# 5DPD8_v1_0_OS_Sheet2.net
KiCad netlist of a schematic drawn in Altium Designer
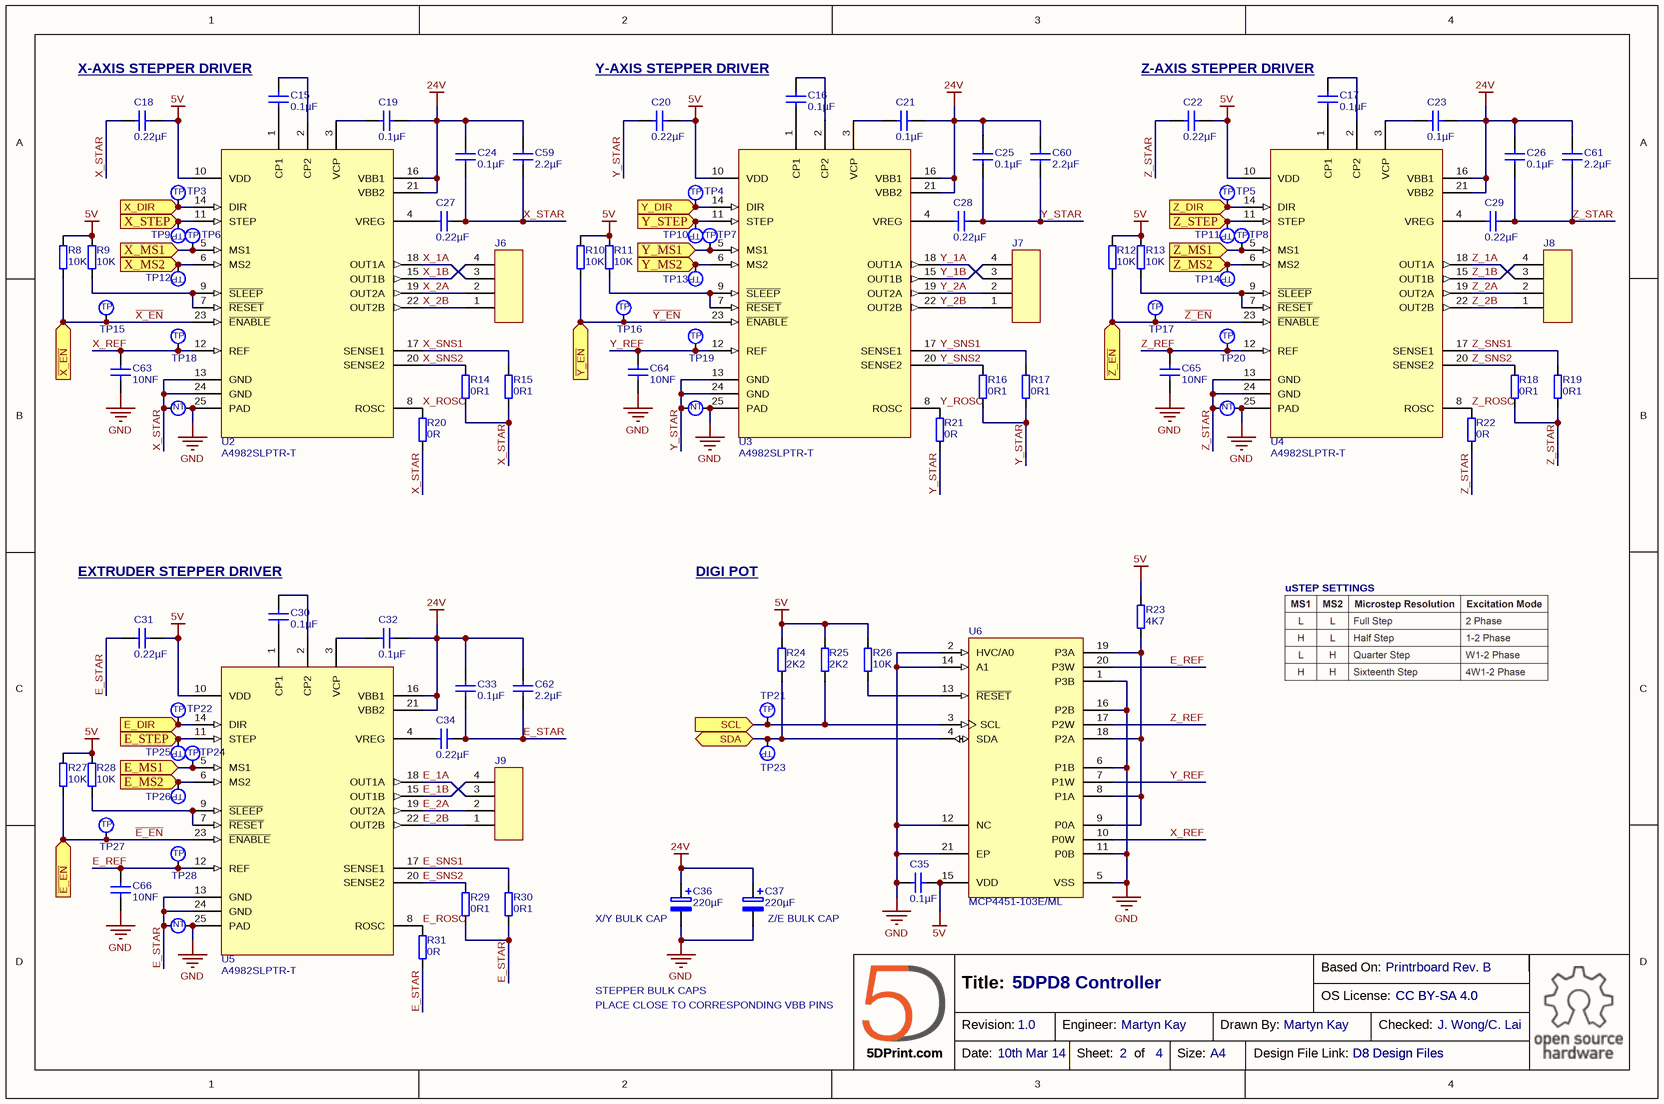
[diagram p0: 5DPD8_v1.0_OS_Sheet2.SchDoc]

(export (version "E")
  (design (tool "Eeschema 10.0.6"))
  (components
    (comp (ref "C15")
      (value "0.1µF")
      (footprint "CAPC0603(1608)100_N")
      (description "CAP CER 0.1UF 50V 10% X7R 0603")
      (fields
        (field (name "MANUFACTURER") "Yageo")
        (field (name "MANUFACTURERPARTNUMBER") "CC0603KRX7R9BB104")
      )
      (libsource (lib "5DPD8") (part "C0603-0.1UF-50V-10%-X7R"))
    )
    (comp (ref "C16")
      (value "0.1µF")
      (footprint "CAPC0603(1608)100_N")
      (description "CAP CER 0.1UF 50V 10% X7R 0603")
      (fields
        (field (name "MANUFACTURER") "Yageo")
        (field (name "MANUFACTURERPARTNUMBER") "CC0603KRX7R9BB104")
      )
      (libsource (lib "5DPD8") (part "C0603-0.1UF-50V-10%-X7R"))
    )
    (comp (ref "C17")
      (value "0.1µF")
      (footprint "CAPC0603(1608)100_N")
      (description "CAP CER 0.1UF 50V 10% X7R 0603")
      (fields
        (field (name "MANUFACTURER") "Yageo")
        (field (name "MANUFACTURERPARTNUMBER") "CC0603KRX7R9BB104")
      )
      (libsource (lib "5DPD8") (part "C0603-0.1UF-50V-10%-X7R"))
    )
    (comp (ref "C18")
      (value "0.22µF")
      (footprint "CAPC0603(1608)100_N")
      (description "CAP CER 0.22UF 50V 10% X7R 0603")
      (fields
        (field (name "MANUFACTURER") "TDK Corporation")
        (field (name "MANUFACTURERPARTNUMBER") "C1608X7R1H224K080AB")
      )
      (libsource (lib "5DPD8") (part "C0603-0.22UF-50V-10%-X7R"))
    )
    (comp (ref "C19")
      (value "0.1µF")
      (footprint "CAPC0603(1608)100_N")
      (description "CAP CER 0.1UF 50V 10% X7R 0603")
      (fields
        (field (name "MANUFACTURER") "Yageo")
        (field (name "MANUFACTURERPARTNUMBER") "CC0603KRX7R9BB104")
      )
      (libsource (lib "5DPD8") (part "C0603-0.1UF-50V-10%-X7R"))
    )
    (comp (ref "C20")
      (value "0.22µF")
      (footprint "CAPC0603(1608)100_N")
      (description "CAP CER 0.22UF 50V 10% X7R 0603")
      (fields
        (field (name "MANUFACTURER") "TDK Corporation")
        (field (name "MANUFACTURERPARTNUMBER") "C1608X7R1H224K080AB")
      )
      (libsource (lib "5DPD8") (part "C0603-0.22UF-50V-10%-X7R"))
    )
    (comp (ref "C21")
      (value "0.1µF")
      (footprint "CAPC0603(1608)100_N")
      (description "CAP CER 0.1UF 50V 10% X7R 0603")
      (fields
        (field (name "MANUFACTURER") "Yageo")
        (field (name "MANUFACTURERPARTNUMBER") "CC0603KRX7R9BB104")
      )
      (libsource (lib "5DPD8") (part "C0603-0.1UF-50V-10%-X7R"))
    )
    (comp (ref "C22")
      (value "0.22µF")
      (footprint "CAPC0603(1608)100_N")
      (description "CAP CER 0.22UF 50V 10% X7R 0603")
      (fields
        (field (name "MANUFACTURER") "TDK Corporation")
        (field (name "MANUFACTURERPARTNUMBER") "C1608X7R1H224K080AB")
      )
      (libsource (lib "5DPD8") (part "C0603-0.22UF-50V-10%-X7R"))
    )
    (comp (ref "C23")
      (value "0.1µF")
      (footprint "CAPC0603(1608)100_N")
      (description "CAP CER 0.1UF 50V 10% X7R 0603")
      (fields
        (field (name "MANUFACTURER") "Yageo")
        (field (name "MANUFACTURERPARTNUMBER") "CC0603KRX7R9BB104")
      )
      (libsource (lib "5DPD8") (part "C0603-0.1UF-50V-10%-X7R"))
    )
    (comp (ref "C24")
      (value "0.1µF")
      (footprint "CAPC0603(1608)100_N")
      (description "CAP CER 0.1UF 50V 10% X7R 0603")
      (fields
        (field (name "MANUFACTURER") "Yageo")
        (field (name "MANUFACTURERPARTNUMBER") "CC0603KRX7R9BB104")
      )
      (libsource (lib "5DPD8") (part "C0603-0.1UF-50V-10%-X7R"))
    )
    (comp (ref "C25")
      (value "0.1µF")
      (footprint "CAPC0603(1608)100_N")
      (description "CAP CER 0.1UF 50V 10% X7R 0603")
      (fields
        (field (name "MANUFACTURER") "Yageo")
        (field (name "MANUFACTURERPARTNUMBER") "CC0603KRX7R9BB104")
      )
      (libsource (lib "5DPD8") (part "C0603-0.1UF-50V-10%-X7R"))
    )
    (comp (ref "C26")
      (value "0.1µF")
      (footprint "CAPC0603(1608)100_N")
      (description "CAP CER 0.1UF 50V 10% X7R 0603")
      (fields
        (field (name "MANUFACTURER") "Yageo")
        (field (name "MANUFACTURERPARTNUMBER") "CC0603KRX7R9BB104")
      )
      (libsource (lib "5DPD8") (part "C0603-0.1UF-50V-10%-X7R"))
    )
    (comp (ref "C27")
      (value "0.22µF")
      (footprint "CAPC0603(1608)100_N")
      (description "CAP CER 0.22UF 50V 10% X7R 0603")
      (fields
        (field (name "MANUFACTURER") "TDK Corporation")
        (field (name "MANUFACTURERPARTNUMBER") "C1608X7R1H224K080AB")
      )
      (libsource (lib "5DPD8") (part "C0603-0.22UF-50V-10%-X7R"))
    )
    (comp (ref "C28")
      (value "0.22µF")
      (footprint "CAPC0603(1608)100_N")
      (description "CAP CER 0.22UF 50V 10% X7R 0603")
      (fields
        (field (name "MANUFACTURER") "TDK Corporation")
        (field (name "MANUFACTURERPARTNUMBER") "C1608X7R1H224K080AB")
      )
      (libsource (lib "5DPD8") (part "C0603-0.22UF-50V-10%-X7R"))
    )
    (comp (ref "C29")
      (value "0.22µF")
      (footprint "CAPC0603(1608)100_N")
      (description "CAP CER 0.22UF 50V 10% X7R 0603")
      (fields
        (field (name "MANUFACTURER") "TDK Corporation")
        (field (name "MANUFACTURERPARTNUMBER") "C1608X7R1H224K080AB")
      )
      (libsource (lib "5DPD8") (part "C0603-0.22UF-50V-10%-X7R"))
    )
    (comp (ref "C30")
      (value "0.1µF")
      (footprint "CAPC0603(1608)100_N")
      (description "CAP CER 0.1UF 50V 10% X7R 0603")
      (fields
        (field (name "MANUFACTURER") "Yageo")
        (field (name "MANUFACTURERPARTNUMBER") "CC0603KRX7R9BB104")
      )
      (libsource (lib "5DPD8") (part "C0603-0.1UF-50V-10%-X7R"))
    )
    (comp (ref "C31")
      (value "0.22µF")
      (footprint "CAPC0603(1608)100_N")
      (description "CAP CER 0.22UF 50V 10% X7R 0603")
      (fields
        (field (name "MANUFACTURER") "TDK Corporation")
        (field (name "MANUFACTURERPARTNUMBER") "C1608X7R1H224K080AB")
      )
      (libsource (lib "5DPD8") (part "C0603-0.22UF-50V-10%-X7R"))
    )
    (comp (ref "C32")
      (value "0.1µF")
      (footprint "CAPC0603(1608)100_N")
      (description "CAP CER 0.1UF 50V 10% X7R 0603")
      (fields
        (field (name "MANUFACTURER") "Yageo")
        (field (name "MANUFACTURERPARTNUMBER") "CC0603KRX7R9BB104")
      )
      (libsource (lib "5DPD8") (part "C0603-0.1UF-50V-10%-X7R"))
    )
    (comp (ref "C33")
      (value "0.1µF")
      (footprint "CAPC0603(1608)100_N")
      (description "CAP CER 0.1UF 50V 10% X7R 0603")
      (fields
        (field (name "MANUFACTURER") "Yageo")
        (field (name "MANUFACTURERPARTNUMBER") "CC0603KRX7R9BB104")
      )
      (libsource (lib "5DPD8") (part "C0603-0.1UF-50V-10%-X7R"))
    )
    (comp (ref "C34")
      (value "0.22µF")
      (footprint "CAPC0603(1608)100_N")
      (description "CAP CER 0.22UF 50V 10% X7R 0603")
      (fields
        (field (name "MANUFACTURER") "TDK Corporation")
        (field (name "MANUFACTURERPARTNUMBER") "C1608X7R1H224K080AB")
      )
      (libsource (lib "5DPD8") (part "C0603-0.22UF-50V-10%-X7R"))
    )
    (comp (ref "C35")
      (value "0.1µF")
      (footprint "CAPC0603(1608)100_N")
      (description "CAP CER 0.1UF 50V 10% X7R 0603")
      (fields
        (field (name "MANUFACTURER") "Yageo")
        (field (name "MANUFACTURERPARTNUMBER") "CC0603KRX7R9BB104")
      )
      (libsource (lib "5DPD8") (part "C0603-0.1UF-50V-10%-X7R"))
    )
    (comp (ref "C36")
      (value "220µF")
      (footprint "CAPRAD8X11.5")
      (description "CAP ALUM 220UF 35V 20% RADIAL")
      (fields
        (field (name "MANUFACTURER") "Rubycon")
        (field (name "MANUFACTURERPARTNUMBER") "35ZLH220MEFC8X11.5")
      )
      (libsource (lib "5DPD8") (part "CAP_RAD-ALU-220UF-35V-20%"))
    )
    (comp (ref "C37")
      (value "220µF")
      (footprint "CAPRAD8X11.5")
      (description "CAP ALUM 220UF 35V 20% RADIAL")
      (fields
        (field (name "MANUFACTURER") "Rubycon")
        (field (name "MANUFACTURERPARTNUMBER") "35ZLH220MEFC8X11.5")
      )
      (libsource (lib "5DPD8") (part "CAP_RAD-ALU-220UF-35V-20%"))
    )
    (comp (ref "C59")
      (value "2.2µF")
      (footprint "CAPC0805(2012)145_N")
      (description "CAP CER 2.2UF 50V 10% X7R 0805")
      (fields
        (field (name "MANUFACTURER") "Taiyo Yuden")
        (field (name "MANUFACTURERPARTNUMBER") "UMK212BB7225KG-T")
      )
      (libsource (lib "5DPD8") (part "C0805-2.2UF-50V-10%-X7R"))
    )
    (comp (ref "C60")
      (value "2.2µF")
      (footprint "CAPC0805(2012)145_N")
      (description "CAP CER 2.2UF 50V 10% X7R 0805")
      (fields
        (field (name "MANUFACTURER") "Taiyo Yuden")
        (field (name "MANUFACTURERPARTNUMBER") "UMK212BB7225KG-T")
      )
      (libsource (lib "5DPD8") (part "C0805-2.2UF-50V-10%-X7R"))
    )
    (comp (ref "C61")
      (value "2.2µF")
      (footprint "CAPC0805(2012)145_N")
      (description "CAP CER 2.2UF 50V 10% X7R 0805")
      (fields
        (field (name "MANUFACTURER") "Taiyo Yuden")
        (field (name "MANUFACTURERPARTNUMBER") "UMK212BB7225KG-T")
      )
      (libsource (lib "5DPD8") (part "C0805-2.2UF-50V-10%-X7R"))
    )
    (comp (ref "C62")
      (value "2.2µF")
      (footprint "CAPC0805(2012)145_N")
      (description "CAP CER 2.2UF 50V 10% X7R 0805")
      (fields
        (field (name "MANUFACTURER") "Taiyo Yuden")
        (field (name "MANUFACTURERPARTNUMBER") "UMK212BB7225KG-T")
      )
      (libsource (lib "5DPD8") (part "C0805-2.2UF-50V-10%-X7R"))
    )
    (comp (ref "C63")
      (value "10NF")
      (footprint "CAPC0603(1608)100_N")
      (description "CAP CER 10000PF 50V 10% X7R 0603")
      (fields
        (field (name "MANUFACTURER") "Yageo")
        (field (name "MANUFACTURERPARTNUMBER") "CC0603KPX7R9BB103")
      )
      (libsource (lib "5DPD8") (part "C0603-10NF-50V-10%-X7R"))
    )
    (comp (ref "C64")
      (value "10NF")
      (footprint "CAPC0603(1608)100_N")
      (description "CAP CER 10000PF 50V 10% X7R 0603")
      (fields
        (field (name "MANUFACTURER") "Yageo")
        (field (name "MANUFACTURERPARTNUMBER") "CC0603KPX7R9BB103")
      )
      (libsource (lib "5DPD8") (part "C0603-10NF-50V-10%-X7R"))
    )
    (comp (ref "C65")
      (value "10NF")
      (footprint "CAPC0603(1608)100_N")
      (description "CAP CER 10000PF 50V 10% X7R 0603")
      (fields
        (field (name "MANUFACTURER") "Yageo")
        (field (name "MANUFACTURERPARTNUMBER") "CC0603KPX7R9BB103")
      )
      (libsource (lib "5DPD8") (part "C0603-10NF-50V-10%-X7R"))
    )
    (comp (ref "C66")
      (value "10NF")
      (footprint "CAPC0603(1608)100_N")
      (description "CAP CER 10000PF 50V 10% X7R 0603")
      (fields
        (field (name "MANUFACTURER") "Yageo")
        (field (name "MANUFACTURERPARTNUMBER") "CC0603KPX7R9BB103")
      )
      (libsource (lib "5DPD8") (part "C0603-10NF-50V-10%-X7R"))
    )
    (comp (ref "J6")
      (value "0022272041")
      (footprint "MOLEX_22-27-2041")
      (description "CONN HEADER 4POS .100 VERT TIN")
      (fields (field (name "MANUFACTURER") "Molex Inc"))
      (libsource (lib "5DPD8") (part "CON_MLX_22-27-2041"))
    )
    (comp (ref "J7")
      (value "0022272041")
      (footprint "MOLEX_22-27-2041")
      (description "CONN HEADER 4POS .100 VERT TIN")
      (fields (field (name "MANUFACTURER") "Molex Inc"))
      (libsource (lib "5DPD8") (part "CON_MLX_22-27-2041"))
    )
    (comp (ref "J8")
      (value "0022272041")
      (footprint "MOLEX_22-27-2041")
      (description "CONN HEADER 4POS .100 VERT TIN")
      (fields (field (name "MANUFACTURER") "Molex Inc"))
      (libsource (lib "5DPD8") (part "CON_MLX_22-27-2041"))
    )
    (comp (ref "J9")
      (value "0022272041")
      (footprint "MOLEX_22-27-2041")
      (description "CONN HEADER 4POS .100 VERT TIN")
      (fields (field (name "MANUFACTURER") "Molex Inc"))
      (libsource (lib "5DPD8") (part "CON_MLX_22-27-2041"))
    )
    (comp (ref "NT2")
      (value "NET_TIE")
      (footprint "NET_TIE-PAD")
      (description "NET TIE")
      (libsource (lib "5DPD8") (part "NET_TIE"))
    )
    (comp (ref "NT3")
      (value "NET_TIE")
      (footprint "NET_TIE-PAD")
      (description "NET TIE")
      (libsource (lib "5DPD8") (part "NET_TIE"))
    )
    (comp (ref "NT4")
      (value "NET_TIE")
      (footprint "NET_TIE-PAD")
      (description "NET TIE")
      (libsource (lib "5DPD8") (part "NET_TIE"))
    )
    (comp (ref "NT5")
      (value "NET_TIE")
      (footprint "NET_TIE-PAD")
      (description "NET TIE")
      (libsource (lib "5DPD8") (part "NET_TIE"))
    )
    (comp (ref "R8")
      (value "10K")
      (footprint "RESC0603(1608)_N")
      (description "RES 10K OHM 1/10W 5% 0603 SMD")
      (fields (field (name "MANUFACTURER") "Yageo") (field (name "MANUFACTURERPARTNUMBER") "RC0603JR-0710KL"))
      (libsource (lib "5DPD8") (part "R0603-10K-0.1W-5%"))
    )
    (comp (ref "R9")
      (value "10K")
      (footprint "RESC0603(1608)_N")
      (description "RES 10K OHM 1/10W 5% 0603 SMD")
      (fields (field (name "MANUFACTURER") "Yageo") (field (name "MANUFACTURERPARTNUMBER") "RC0603JR-0710KL"))
      (libsource (lib "5DPD8") (part "R0603-10K-0.1W-5%"))
    )
    (comp (ref "R10")
      (value "10K")
      (footprint "RESC0603(1608)_N")
      (description "RES 10K OHM 1/10W 5% 0603 SMD")
      (fields (field (name "MANUFACTURER") "Yageo") (field (name "MANUFACTURERPARTNUMBER") "RC0603JR-0710KL"))
      (libsource (lib "5DPD8") (part "R0603-10K-0.1W-5%"))
    )
    (comp (ref "R11")
      (value "10K")
      (footprint "RESC0603(1608)_N")
      (description "RES 10K OHM 1/10W 5% 0603 SMD")
      (fields (field (name "MANUFACTURER") "Yageo") (field (name "MANUFACTURERPARTNUMBER") "RC0603JR-0710KL"))
      (libsource (lib "5DPD8") (part "R0603-10K-0.1W-5%"))
    )
    (comp (ref "R12")
      (value "10K")
      (footprint "RESC0603(1608)_N")
      (description "RES 10K OHM 1/10W 5% 0603 SMD")
      (fields (field (name "MANUFACTURER") "Yageo") (field (name "MANUFACTURERPARTNUMBER") "RC0603JR-0710KL"))
      (libsource (lib "5DPD8") (part "R0603-10K-0.1W-5%"))
    )
    (comp (ref "R13")
      (value "10K")
      (footprint "RESC0603(1608)_N")
      (description "RES 10K OHM 1/10W 5% 0603 SMD")
      (fields (field (name "MANUFACTURER") "Yageo") (field (name "MANUFACTURERPARTNUMBER") "RC0603JR-0710KL"))
      (libsource (lib "5DPD8") (part "R0603-10K-0.1W-5%"))
    )
    (comp (ref "R14")
      (value "0R1")
      (footprint "RESC0805(2012)_L")
      (description "RES 0.100 OHM 0.5W 1% 0805")
      (fields
        (field (name "MANUFACTURER") "Susumu")
        (field (name "MANUFACTURERPARTNUMBER") "KRL1220E-M-R100-F-T5")
      )
      (libsource (lib "5DPD8") (part "R0805-0R1-0.5W-1%"))
    )
    (comp (ref "R15")
      (value "0R1")
      (footprint "RESC0805(2012)_L")
      (description "RES 0.100 OHM 0.5W 1% 0805")
      (fields
        (field (name "MANUFACTURER") "Susumu")
        (field (name "MANUFACTURERPARTNUMBER") "KRL1220E-M-R100-F-T5")
      )
      (libsource (lib "5DPD8") (part "R0805-0R1-0.5W-1%"))
    )
    (comp (ref "R16")
      (value "0R1")
      (footprint "RESC0805(2012)_L")
      (description "RES 0.100 OHM 0.5W 1% 0805")
      (fields
        (field (name "MANUFACTURER") "Susumu")
        (field (name "MANUFACTURERPARTNUMBER") "KRL1220E-M-R100-F-T5")
      )
      (libsource (lib "5DPD8") (part "R0805-0R1-0.5W-1%"))
    )
    (comp (ref "R17")
      (value "0R1")
      (footprint "RESC0805(2012)_L")
      (description "RES 0.100 OHM 0.5W 1% 0805")
      (fields
        (field (name "MANUFACTURER") "Susumu")
        (field (name "MANUFACTURERPARTNUMBER") "KRL1220E-M-R100-F-T5")
      )
      (libsource (lib "5DPD8") (part "R0805-0R1-0.5W-1%"))
    )
    (comp (ref "R18")
      (value "0R1")
      (footprint "RESC0805(2012)_L")
      (description "RES 0.100 OHM 0.5W 1% 0805")
      (fields
        (field (name "MANUFACTURER") "Susumu")
        (field (name "MANUFACTURERPARTNUMBER") "KRL1220E-M-R100-F-T5")
      )
      (libsource (lib "5DPD8") (part "R0805-0R1-0.5W-1%"))
    )
    (comp (ref "R19")
      (value "0R1")
      (footprint "RESC0805(2012)_L")
      (description "RES 0.100 OHM 0.5W 1% 0805")
      (fields
        (field (name "MANUFACTURER") "Susumu")
        (field (name "MANUFACTURERPARTNUMBER") "KRL1220E-M-R100-F-T5")
      )
      (libsource (lib "5DPD8") (part "R0805-0R1-0.5W-1%"))
    )
    (comp (ref "R20")
      (value "0R")
      (footprint "RESC0603(1608)_N")
      (description "RES ZERO OHM 1/10W JUMP 0603 SMD")
      (fields (field (name "MANUFACTURER") "Yageo") (field (name "MANUFACTURERPARTNUMBER") "RC0603JR-070RL"))
      (libsource (lib "5DPD8") (part "R0603-0R-0.1W-JUMP"))
    )
    (comp (ref "R21")
      (value "0R")
      (footprint "RESC0603(1608)_N")
      (description "RES ZERO OHM 1/10W JUMP 0603 SMD")
      (fields (field (name "MANUFACTURER") "Yageo") (field (name "MANUFACTURERPARTNUMBER") "RC0603JR-070RL"))
      (libsource (lib "5DPD8") (part "R0603-0R-0.1W-JUMP"))
    )
    (comp (ref "R22")
      (value "0R")
      (footprint "RESC0603(1608)_N")
      (description "RES ZERO OHM 1/10W JUMP 0603 SMD")
      (fields (field (name "MANUFACTURER") "Yageo") (field (name "MANUFACTURERPARTNUMBER") "RC0603JR-070RL"))
      (libsource (lib "5DPD8") (part "R0603-0R-0.1W-JUMP"))
    )
    (comp (ref "R23")
      (value "4K7")
      (footprint "RESC0603(1608)_N")
      (description "RES 4.70K OHM 1/10W 1% 0603 SMD")
      (fields (field (name "MANUFACTURER") "Yageo") (field (name "MANUFACTURERPARTNUMBER") "RC0603FR-074K7L"))
      (libsource (lib "5DPD8") (part "R0603-4K7-0.1W-1%"))
    )
    (comp (ref "R24")
      (value "2K2")
      (footprint "RESC0603(1608)_N")
      (description "RES 2.2K OHM 1/10W 5% 0603 SMD")
      (fields (field (name "MANUFACTURER") "Yageo") (field (name "MANUFACTURERPARTNUMBER") "RC0603JR-072K2L"))
      (libsource (lib "5DPD8") (part "R0603-2K2-0.1W-5%"))
    )
    (comp (ref "R25")
      (value "2K2")
      (footprint "RESC0603(1608)_N")
      (description "RES 2.2K OHM 1/10W 5% 0603 SMD")
      (fields (field (name "MANUFACTURER") "Yageo") (field (name "MANUFACTURERPARTNUMBER") "RC0603JR-072K2L"))
      (libsource (lib "5DPD8") (part "R0603-2K2-0.1W-5%"))
    )
    (comp (ref "R26")
      (value "10K")
      (footprint "RESC0603(1608)_N")
      (description "RES 10K OHM 1/10W 5% 0603 SMD")
      (fields (field (name "MANUFACTURER") "Yageo") (field (name "MANUFACTURERPARTNUMBER") "RC0603JR-0710KL"))
      (libsource (lib "5DPD8") (part "R0603-10K-0.1W-5%"))
    )
    (comp (ref "R27")
      (value "10K")
      (footprint "RESC0603(1608)_N")
      (description "RES 10K OHM 1/10W 5% 0603 SMD")
      (fields (field (name "MANUFACTURER") "Yageo") (field (name "MANUFACTURERPARTNUMBER") "RC0603JR-0710KL"))
      (libsource (lib "5DPD8") (part "R0603-10K-0.1W-5%"))
    )
    (comp (ref "R28")
      (value "10K")
      (footprint "RESC0603(1608)_N")
      (description "RES 10K OHM 1/10W 5% 0603 SMD")
      (fields (field (name "MANUFACTURER") "Yageo") (field (name "MANUFACTURERPARTNUMBER") "RC0603JR-0710KL"))
      (libsource (lib "5DPD8") (part "R0603-10K-0.1W-5%"))
    )
    (comp (ref "R29")
      (value "0R1")
      (footprint "RESC0805(2012)_L")
      (description "RES 0.100 OHM 0.5W 1% 0805")
      (fields
        (field (name "MANUFACTURER") "Susumu")
        (field (name "MANUFACTURERPARTNUMBER") "KRL1220E-M-R100-F-T5")
      )
      (libsource (lib "5DPD8") (part "R0805-0R1-0.5W-1%"))
    )
    (comp (ref "R30")
      (value "0R1")
      (footprint "RESC0805(2012)_L")
      (description "RES 0.100 OHM 0.5W 1% 0805")
      (fields
        (field (name "MANUFACTURER") "Susumu")
        (field (name "MANUFACTURERPARTNUMBER") "KRL1220E-M-R100-F-T5")
      )
      (libsource (lib "5DPD8") (part "R0805-0R1-0.5W-1%"))
    )
    (comp (ref "R31")
      (value "0R")
      (footprint "RESC0603(1608)_N")
      (description "RES ZERO OHM 1/10W JUMP 0603 SMD")
      (fields (field (name "MANUFACTURER") "Yageo") (field (name "MANUFACTURERPARTNUMBER") "RC0603JR-070RL"))
      (libsource (lib "5DPD8") (part "R0603-0R-0.1W-JUMP"))
    )
    (comp (ref "TP3")
      (value "TESTPOINT")
      (footprint "TESTPOINT")
      (libsource (lib "5DPD8") (part "TESTPOINT"))
    )
    (comp (ref "TP4")
      (value "TESTPOINT")
      (footprint "TESTPOINT")
      (libsource (lib "5DPD8") (part "TESTPOINT"))
    )
    (comp (ref "TP5")
      (value "TESTPOINT")
      (footprint "TESTPOINT")
      (libsource (lib "5DPD8") (part "TESTPOINT"))
    )
    (comp (ref "TP6")
      (value "TESTPOINT")
      (footprint "TESTPOINT")
      (libsource (lib "5DPD8") (part "TESTPOINT"))
    )
    (comp (ref "TP7")
      (value "TESTPOINT")
      (footprint "TESTPOINT")
      (libsource (lib "5DPD8") (part "TESTPOINT"))
    )
    (comp (ref "TP8")
      (value "TESTPOINT")
      (footprint "TESTPOINT")
      (libsource (lib "5DPD8") (part "TESTPOINT"))
    )
    (comp (ref "TP9")
      (value "TESTPOINT")
      (footprint "TESTPOINT")
      (libsource (lib "5DPD8") (part "TESTPOINT"))
    )
    (comp (ref "TP10")
      (value "TESTPOINT")
      (footprint "TESTPOINT")
      (libsource (lib "5DPD8") (part "TESTPOINT"))
    )
    (comp (ref "TP11")
      (value "TESTPOINT")
      (footprint "TESTPOINT")
      (libsource (lib "5DPD8") (part "TESTPOINT"))
    )
    (comp (ref "TP12")
      (value "TESTPOINT")
      (footprint "TESTPOINT")
      (libsource (lib "5DPD8") (part "TESTPOINT"))
    )
    (comp (ref "TP13")
      (value "TESTPOINT")
      (footprint "TESTPOINT")
      (libsource (lib "5DPD8") (part "TESTPOINT"))
    )
    (comp (ref "TP14")
      (value "TESTPOINT")
      (footprint "TESTPOINT")
      (libsource (lib "5DPD8") (part "TESTPOINT"))
    )
    (comp (ref "TP15")
      (value "TESTPOINT")
      (footprint "TESTPOINT")
      (libsource (lib "5DPD8") (part "TESTPOINT"))
    )
    (comp (ref "TP16")
      (value "TESTPOINT")
      (footprint "TESTPOINT")
      (libsource (lib "5DPD8") (part "TESTPOINT"))
    )
    (comp (ref "TP17")
      (value "TESTPOINT")
      (footprint "TESTPOINT")
      (libsource (lib "5DPD8") (part "TESTPOINT"))
    )
    (comp (ref "TP18")
      (value "TESTPOINT")
      (footprint "TESTPOINT")
      (libsource (lib "5DPD8") (part "TESTPOINT"))
    )
    (comp (ref "TP19")
      (value "TESTPOINT")
      (footprint "TESTPOINT")
      (libsource (lib "5DPD8") (part "TESTPOINT"))
    )
    (comp (ref "TP20")
      (value "TESTPOINT")
      (footprint "TESTPOINT")
      (libsource (lib "5DPD8") (part "TESTPOINT"))
    )
    (comp (ref "TP21")
      (value "TESTPOINT")
      (footprint "TESTPOINT")
      (libsource (lib "5DPD8") (part "TESTPOINT"))
    )
    (comp (ref "TP22")
      (value "TESTPOINT")
      (footprint "TESTPOINT")
      (libsource (lib "5DPD8") (part "TESTPOINT"))
    )
    (comp (ref "TP23")
      (value "TESTPOINT")
      (footprint "TESTPOINT")
      (libsource (lib "5DPD8") (part "TESTPOINT"))
    )
    (comp (ref "TP24")
      (value "TESTPOINT")
      (footprint "TESTPOINT")
      (libsource (lib "5DPD8") (part "TESTPOINT"))
    )
    (comp (ref "TP25")
      (value "TESTPOINT")
      (footprint "TESTPOINT")
      (libsource (lib "5DPD8") (part "TESTPOINT"))
    )
    (comp (ref "TP26")
      (value "TESTPOINT")
      (footprint "TESTPOINT")
      (libsource (lib "5DPD8") (part "TESTPOINT"))
    )
    (comp (ref "TP27")
      (value "TESTPOINT")
      (footprint "TESTPOINT")
      (libsource (lib "5DPD8") (part "TESTPOINT"))
    )
    (comp (ref "TP28")
      (value "TESTPOINT")
      (footprint "TESTPOINT")
      (libsource (lib "5DPD8") (part "TESTPOINT"))
    )
    (comp (ref "U2")
      (value "A4982SLPTR-T")
      (footprint "TSOP65P640X120_HS-25N")
      (description "IC MOTOR DRIVER PAR 24TSSOP")
      (fields (field (name "MANUFACTURER") "Allegro MicroSystems, LLC"))
      (libsource (lib "5DPD8") (part "IC_A4982SLPTR-T"))
    )
    (comp (ref "U3")
      (value "A4982SLPTR-T")
      (footprint "TSOP65P640X120_HS-25N")
      (description "IC MOTOR DRIVER PAR 24TSSOP")
      (fields (field (name "MANUFACTURER") "Allegro MicroSystems, LLC"))
      (libsource (lib "5DPD8") (part "IC_A4982SLPTR-T"))
    )
    (comp (ref "U4")
      (value "A4982SLPTR-T")
      (footprint "TSOP65P640X120_HS-25N")
      (description "IC MOTOR DRIVER PAR 24TSSOP")
      (fields (field (name "MANUFACTURER") "Allegro MicroSystems, LLC"))
      (libsource (lib "5DPD8") (part "IC_A4982SLPTR-T"))
    )
    (comp (ref "U5")
      (value "A4982SLPTR-T")
      (footprint "TSOP65P640X120_HS-25N")
      (description "IC MOTOR DRIVER PAR 24TSSOP")
      (fields (field (name "MANUFACTURER") "Allegro MicroSystems, LLC"))
      (libsource (lib "5DPD8") (part "IC_A4982SLPTR-T"))
    )
    (comp (ref "U6")
      (value "MCP4451-103E/ML")
      (footprint "QFN-ML20_N")
      (description "IC POT 10K QUAD 8BIT 20QFN")
      (fields (field (name "MANUFACTURER") "Microchip Technology"))
      (libsource (lib "5DPD8") (part "IC_MCP4451-103E/ML"))
    )
  )
  (nets
    (net (code "1") (name "/E_1A") (class "Default")
      (node (ref "J9") (pin "3") (pinfunction "3_3") (pintype "passive"))
      (node (ref "U5") (pin "18") (pinfunction "OUT1A_18") (pintype "output"))
    )
    (net (code "2") (name "/E_1B") (class "Default")
      (node (ref "J9") (pin "4") (pinfunction "4_4") (pintype "passive"))
      (node (ref "U5") (pin "15") (pinfunction "OUT1B_15") (pintype "output"))
    )
    (net (code "3") (name "/E_2A") (class "Default")
      (node (ref "J9") (pin "2") (pinfunction "2_2") (pintype "passive"))
      (node (ref "U5") (pin "19") (pinfunction "OUT2A_19") (pintype "output"))
    )
    (net (code "4") (name "/E_2B") (class "Default")
      (node (ref "J9") (pin "1") (pinfunction "1_1") (pintype "passive"))
      (node (ref "U5") (pin "22") (pinfunction "OUT2B_22") (pintype "output"))
    )
    (net (code "5") (name "/E_DIR") (class "Default")
      (node (ref "TP22") (pin "1") (pinfunction "1_1") (pintype "passive"))
      (node (ref "U5") (pin "14") (pinfunction "DIR_14") (pintype "input"))
    )
    (net (code "6") (name "/E_MS1") (class "Default")
      (node (ref "TP24") (pin "1") (pinfunction "1_1") (pintype "passive"))
      (node (ref "U5") (pin "5") (pinfunction "MS1_5") (pintype "input"))
    )
    (net (code "7") (name "/E_MS2") (class "Default")
      (node (ref "TP26") (pin "1") (pinfunction "1_1") (pintype "passive"))
      (node (ref "U5") (pin "6") (pinfunction "MS2_6") (pintype "input"))
    )
    (net (code "8") (name "/E_REF") (class "Default")
      (node (ref "C66") (pin "2") (pinfunction "2_2") (pintype "passive"))
      (node (ref "TP28") (pin "1") (pinfunction "1_1") (pintype "passive"))
      (node (ref "U5") (pin "12") (pinfunction "REF_12") (pintype "input"))
      (node (ref "U6") (pin "20") (pinfunction "P3W_20") (pintype "passive"))
    )
    (net (code "9") (name "/E_ROSC") (class "Default")
      (node (ref "R31") (pin "2") (pinfunction "2_2") (pintype "passive"))
      (node (ref "U5") (pin "8") (pinfunction "ROSC_8") (pintype "passive"))
    )
    (net (code "10") (name "/E_SNS1") (class "Default")
      (node (ref "R30") (pin "2") (pinfunction "2_2") (pintype "passive"))
      (node (ref "U5") (pin "17") (pinfunction "SENSE1_17") (pintype "passive"))
    )
    (net (code "11") (name "/E_SNS2") (class "Default")
      (node (ref "R29") (pin "2") (pinfunction "2_2") (pintype "passive"))
      (node (ref "U5") (pin "20") (pinfunction "SENSE2_20") (pintype "passive"))
    )
    (net (code "12") (name "/E_STAR") (class "Default")
      (node (ref "C31") (pin "1") (pinfunction "1_1") (pintype "passive"))
      (node (ref "C33") (pin "1") (pinfunction "1_1") (pintype "passive"))
      (node (ref "C34") (pin "2") (pinfunction "2_2") (pintype "passive"))
      (node (ref "C62") (pin "1") (pinfunction "1_1") (pintype "passive"))
      (node (ref "NT5") (pin "1") (pinfunction "1_1") (pintype "passive"))
      (node (ref "R29") (pin "1") (pinfunction "1_1") (pintype "passive"))
      (node (ref "R30") (pin "1") (pinfunction "1_1") (pintype "passive"))
      (node (ref "R31") (pin "1") (pinfunction "1_1") (pintype "passive"))
      (node (ref "U5") (pin "13") (pinfunction "GND_13") (pintype "power_in"))
      (node (ref "U5") (pin "24") (pinfunction "GND_24") (pintype "power_in"))
    )
    (net (code "13") (name "/E_STEP") (class "Default")
      (node (ref "TP25") (pin "1") (pinfunction "1_1") (pintype "passive"))
      (node (ref "U5") (pin "11") (pinfunction "STEP_11") (pintype "input"))
    )
    (net (code "14") (name "/SCL") (class "Default")
      (node (ref "R25") (pin "1") (pinfunction "1_1") (pintype "passive"))
      (node (ref "TP21") (pin "1") (pinfunction "1_1") (pintype "passive"))
      (node (ref "U6") (pin "3") (pinfunction "SCL_3") (pintype "input"))
    )
    (net (code "15") (name "/SDA") (class "Default")
      (node (ref "R24") (pin "1") (pinfunction "1_1") (pintype "passive"))
      (node (ref "TP23") (pin "1") (pinfunction "1_1") (pintype "passive"))
      (node (ref "U6") (pin "4") (pinfunction "SDA_4") (pintype "bidirectional"))
    )
    (net (code "16") (name "/X_1A") (class "Default")
      (node (ref "J6") (pin "3") (pinfunction "3_3") (pintype "passive"))
      (node (ref "U2") (pin "18") (pinfunction "OUT1A_18") (pintype "output"))
    )
    (net (code "17") (name "/X_1B") (class "Default")
      (node (ref "J6") (pin "4") (pinfunction "4_4") (pintype "passive"))
      (node (ref "U2") (pin "15") (pinfunction "OUT1B_15") (pintype "output"))
    )
    (net (code "18") (name "/X_2A") (class "Default")
      (node (ref "J6") (pin "2") (pinfunction "2_2") (pintype "passive"))
      (node (ref "U2") (pin "19") (pinfunction "OUT2A_19") (pintype "output"))
    )
    (net (code "19") (name "/X_2B") (class "Default")
      (node (ref "J6") (pin "1") (pinfunction "1_1") (pintype "passive"))
      (node (ref "U2") (pin "22") (pinfunction "OUT2B_22") (pintype "output"))
    )
    (net (code "20") (name "/X_DIR") (class "Default")
      (node (ref "TP3") (pin "1") (pinfunction "1_1") (pintype "passive"))
      (node (ref "U2") (pin "14") (pinfunction "DIR_14") (pintype "input"))
    )
    (net (code "21") (name "/X_MS1") (class "Default")
      (node (ref "TP6") (pin "1") (pinfunction "1_1") (pintype "passive"))
      (node (ref "U2") (pin "5") (pinfunction "MS1_5") (pintype "input"))
    )
    (net (code "22") (name "/X_MS2") (class "Default")
      (node (ref "TP12") (pin "1") (pinfunction "1_1") (pintype "passive"))
      (node (ref "U2") (pin "6") (pinfunction "MS2_6") (pintype "input"))
    )
    (net (code "23") (name "/X_REF") (class "Default")
      (node (ref "C63") (pin "2") (pinfunction "2_2") (pintype "passive"))
      (node (ref "TP18") (pin "1") (pinfunction "1_1") (pintype "passive"))
      (node (ref "U2") (pin "12") (pinfunction "REF_12") (pintype "input"))
      (node (ref "U6") (pin "10") (pinfunction "P0W_10") (pintype "passive"))
    )
    (net (code "24") (name "/X_ROSC") (class "Default")
      (node (ref "R20") (pin "2") (pinfunction "2_2") (pintype "passive"))
      (node (ref "U2") (pin "8") (pinfunction "ROSC_8") (pintype "passive"))
    )
    (net (code "25") (name "/X_SNS1") (class "Default")
      (node (ref "R15") (pin "2") (pinfunction "2_2") (pintype "passive"))
      (node (ref "U2") (pin "17") (pinfunction "SENSE1_17") (pintype "passive"))
    )
    (net (code "26") (name "/X_SNS2") (class "Default")
      (node (ref "R14") (pin "2") (pinfunction "2_2") (pintype "passive"))
      (node (ref "U2") (pin "20") (pinfunction "SENSE2_20") (pintype "passive"))
    )
    (net (code "27") (name "/X_STAR") (class "Default")
      (node (ref "C18") (pin "1") (pinfunction "1_1") (pintype "passive"))
      (node (ref "C24") (pin "1") (pinfunction "1_1") (pintype "passive"))
      (node (ref "C27") (pin "2") (pinfunction "2_2") (pintype "passive"))
      (node (ref "C59") (pin "1") (pinfunction "1_1") (pintype "passive"))
      (node (ref "NT2") (pin "1") (pinfunction "1_1") (pintype "passive"))
      (node (ref "R14") (pin "1") (pinfunction "1_1") (pintype "passive"))
      (node (ref "R15") (pin "1") (pinfunction "1_1") (pintype "passive"))
      (node (ref "R20") (pin "1") (pinfunction "1_1") (pintype "passive"))
      (node (ref "U2") (pin "13") (pinfunction "GND_13") (pintype "power_in"))
      (node (ref "U2") (pin "24") (pinfunction "GND_24") (pintype "power_in"))
    )
    (net (code "28") (name "/X_STEP") (class "Default")
      (node (ref "TP9") (pin "1") (pinfunction "1_1") (pintype "passive"))
      (node (ref "U2") (pin "11") (pinfunction "STEP_11") (pintype "input"))
    )
    (net (code "29") (name "/Y_1A") (class "Default")
      (node (ref "J7") (pin "3") (pinfunction "3_3") (pintype "passive"))
      (node (ref "U3") (pin "18") (pinfunction "OUT1A_18") (pintype "output"))
    )
    (net (code "30") (name "/Y_1B") (class "Default")
      (node (ref "J7") (pin "4") (pinfunction "4_4") (pintype "passive"))
      (node (ref "U3") (pin "15") (pinfunction "OUT1B_15") (pintype "output"))
    )
    (net (code "31") (name "/Y_2A") (class "Default")
      (node (ref "J7") (pin "2") (pinfunction "2_2") (pintype "passive"))
      (node (ref "U3") (pin "19") (pinfunction "OUT2A_19") (pintype "output"))
    )
    (net (code "32") (name "/Y_2B") (class "Default")
      (node (ref "J7") (pin "1") (pinfunction "1_1") (pintype "passive"))
      (node (ref "U3") (pin "22") (pinfunction "OUT2B_22") (pintype "output"))
    )
    (net (code "33") (name "/Y_DIR") (class "Default")
      (node (ref "TP4") (pin "1") (pinfunction "1_1") (pintype "passive"))
      (node (ref "U3") (pin "14") (pinfunction "DIR_14") (pintype "input"))
    )
    (net (code "34") (name "/Y_MS1") (class "Default")
      (node (ref "TP7") (pin "1") (pinfunction "1_1") (pintype "passive"))
      (node (ref "U3") (pin "5") (pinfunction "MS1_5") (pintype "input"))
    )
    (net (code "35") (name "/Y_MS2") (class "Default")
      (node (ref "TP13") (pin "1") (pinfunction "1_1") (pintype "passive"))
      (node (ref "U3") (pin "6") (pinfunction "MS2_6") (pintype "input"))
    )
    (net (code "36") (name "/Y_REF") (class "Default")
      (node (ref "C64") (pin "2") (pinfunction "2_2") (pintype "passive"))
      (node (ref "TP19") (pin "1") (pinfunction "1_1") (pintype "passive"))
      (node (ref "U3") (pin "12") (pinfunction "REF_12") (pintype "input"))
      (node (ref "U6") (pin "7") (pinfunction "P1W_7") (pintype "passive"))
    )
    (net (code "37") (name "/Y_ROSC") (class "Default")
      (node (ref "R21") (pin "2") (pinfunction "2_2") (pintype "passive"))
      (node (ref "U3") (pin "8") (pinfunction "ROSC_8") (pintype "passive"))
    )
    (net (code "38") (name "/Y_SNS1") (class "Default")
      (node (ref "R17") (pin "2") (pinfunction "2_2") (pintype "passive"))
      (node (ref "U3") (pin "17") (pinfunction "SENSE1_17") (pintype "passive"))
    )
    (net (code "39") (name "/Y_SNS2") (class "Default")
      (node (ref "R16") (pin "2") (pinfunction "2_2") (pintype "passive"))
      (node (ref "U3") (pin "20") (pinfunction "SENSE2_20") (pintype "passive"))
    )
    (net (code "40") (name "/Y_STAR") (class "Default")
      (node (ref "C20") (pin "1") (pinfunction "1_1") (pintype "passive"))
      (node (ref "C25") (pin "1") (pinfunction "1_1") (pintype "passive"))
      (node (ref "C28") (pin "2") (pinfunction "2_2") (pintype "passive"))
      (node (ref "C60") (pin "1") (pinfunction "1_1") (pintype "passive"))
      (node (ref "NT3") (pin "1") (pinfunction "1_1") (pintype "passive"))
      (node (ref "R16") (pin "1") (pinfunction "1_1") (pintype "passive"))
      (node (ref "R17") (pin "1") (pinfunction "1_1") (pintype "passive"))
      (node (ref "R21") (pin "1") (pinfunction "1_1") (pintype "passive"))
      (node (ref "U3") (pin "13") (pinfunction "GND_13") (pintype "power_in"))
      (node (ref "U3") (pin "24") (pinfunction "GND_24") (pintype "power_in"))
    )
    (net (code "41") (name "/Y_STEP") (class "Default")
      (node (ref "TP10") (pin "1") (pinfunction "1_1") (pintype "passive"))
      (node (ref "U3") (pin "11") (pinfunction "STEP_11") (pintype "input"))
    )
    (net (code "42") (name "/Z_1A") (class "Default")
      (node (ref "J8") (pin "3") (pinfunction "3_3") (pintype "passive"))
      (node (ref "U4") (pin "18") (pinfunction "OUT1A_18") (pintype "output"))
    )
    (net (code "43") (name "/Z_1B") (class "Default")
      (node (ref "J8") (pin "4") (pinfunction "4_4") (pintype "passive"))
      (node (ref "U4") (pin "15") (pinfunction "OUT1B_15") (pintype "output"))
    )
    (net (code "44") (name "/Z_2A") (class "Default")
      (node (ref "J8") (pin "2") (pinfunction "2_2") (pintype "passive"))
      (node (ref "U4") (pin "19") (pinfunction "OUT2A_19") (pintype "output"))
    )
    (net (code "45") (name "/Z_2B") (class "Default")
      (node (ref "J8") (pin "1") (pinfunction "1_1") (pintype "passive"))
      (node (ref "U4") (pin "22") (pinfunction "OUT2B_22") (pintype "output"))
    )
    (net (code "46") (name "/Z_DIR") (class "Default")
      (node (ref "TP5") (pin "1") (pinfunction "1_1") (pintype "passive"))
      (node (ref "U4") (pin "14") (pinfunction "DIR_14") (pintype "input"))
    )
    (net (code "47") (name "/Z_MS1") (class "Default")
      (node (ref "TP8") (pin "1") (pinfunction "1_1") (pintype "passive"))
      (node (ref "U4") (pin "5") (pinfunction "MS1_5") (pintype "input"))
    )
    (net (code "48") (name "/Z_MS2") (class "Default")
      (node (ref "TP14") (pin "1") (pinfunction "1_1") (pintype "passive"))
      (node (ref "U4") (pin "6") (pinfunction "MS2_6") (pintype "input"))
    )
    (net (code "49") (name "/Z_REF") (class "Default")
      (node (ref "C65") (pin "2") (pinfunction "2_2") (pintype "passive"))
      (node (ref "TP20") (pin "1") (pinfunction "1_1") (pintype "passive"))
      (node (ref "U4") (pin "12") (pinfunction "REF_12") (pintype "input"))
      (node (ref "U6") (pin "17") (pinfunction "P2W_17") (pintype "passive"))
    )
    (net (code "50") (name "/Z_ROSC") (class "Default")
      (node (ref "R22") (pin "2") (pinfunction "2_2") (pintype "passive"))
      (node (ref "U4") (pin "8") (pinfunction "ROSC_8") (pintype "passive"))
    )
    (net (code "51") (name "/Z_SNS1") (class "Default")
      (node (ref "R19") (pin "2") (pinfunction "2_2") (pintype "passive"))
      (node (ref "U4") (pin "17") (pinfunction "SENSE1_17") (pintype "passive"))
    )
    (net (code "52") (name "/Z_SNS2") (class "Default")
      (node (ref "R18") (pin "2") (pinfunction "2_2") (pintype "passive"))
      (node (ref "U4") (pin "20") (pinfunction "SENSE2_20") (pintype "passive"))
    )
    (net (code "53") (name "/Z_STAR") (class "Default")
      (node (ref "C22") (pin "1") (pinfunction "1_1") (pintype "passive"))
      (node (ref "C26") (pin "1") (pinfunction "1_1") (pintype "passive"))
      (node (ref "C29") (pin "2") (pinfunction "2_2") (pintype "passive"))
      (node (ref "C61") (pin "1") (pinfunction "1_1") (pintype "passive"))
      (node (ref "NT4") (pin "1") (pinfunction "1_1") (pintype "passive"))
      (node (ref "R18") (pin "1") (pinfunction "1_1") (pintype "passive"))
      (node (ref "R19") (pin "1") (pinfunction "1_1") (pintype "passive"))
      (node (ref "R22") (pin "1") (pinfunction "1_1") (pintype "passive"))
      (node (ref "U4") (pin "13") (pinfunction "GND_13") (pintype "power_in"))
      (node (ref "U4") (pin "24") (pinfunction "GND_24") (pintype "power_in"))
    )
    (net (code "54") (name "/Z_STEP") (class "Default")
      (node (ref "TP11") (pin "1") (pinfunction "1_1") (pintype "passive"))
      (node (ref "U4") (pin "11") (pinfunction "STEP_11") (pintype "input"))
    )
    (net (code "55") (name "/~{E_EN}") (class "Default")
      (node (ref "R27") (pin "1") (pinfunction "1_1") (pintype "passive"))
      (node (ref "TP27") (pin "1") (pinfunction "1_1") (pintype "passive"))
      (node (ref "U5") (pin "23") (pinfunction "~{ENABLE}_23") (pintype "input"))
    )
    (net (code "56") (name "/~{X_EN}") (class "Default")
      (node (ref "R8") (pin "1") (pinfunction "1_1") (pintype "passive"))
      (node (ref "TP15") (pin "1") (pinfunction "1_1") (pintype "passive"))
      (node (ref "U2") (pin "23") (pinfunction "~{ENABLE}_23") (pintype "input"))
    )
    (net (code "57") (name "/~{Y_EN}") (class "Default")
      (node (ref "R10") (pin "1") (pinfunction "1_1") (pintype "passive"))
      (node (ref "TP16") (pin "1") (pinfunction "1_1") (pintype "passive"))
      (node (ref "U3") (pin "23") (pinfunction "~{ENABLE}_23") (pintype "input"))
    )
    (net (code "58") (name "/~{Z_EN}") (class "Default")
      (node (ref "R12") (pin "1") (pinfunction "1_1") (pintype "passive"))
      (node (ref "TP17") (pin "1") (pinfunction "1_1") (pintype "passive"))
      (node (ref "U4") (pin "23") (pinfunction "~{ENABLE}_23") (pintype "input"))
    )
    (net (code "59") (name "5V") (class "Default")
      (node (ref "C18") (pin "2") (pinfunction "2_2") (pintype "passive"))
      (node (ref "C20") (pin "2") (pinfunction "2_2") (pintype "passive"))
      (node (ref "C22") (pin "2") (pinfunction "2_2") (pintype "passive"))
      (node (ref "C31") (pin "2") (pinfunction "2_2") (pintype "passive"))
      (node (ref "C35") (pin "2") (pinfunction "2_2") (pintype "passive"))
      (node (ref "R10") (pin "2") (pinfunction "2_2") (pintype "passive"))
      (node (ref "R11") (pin "2") (pinfunction "2_2") (pintype "passive"))
      (node (ref "R12") (pin "2") (pinfunction "2_2") (pintype "passive"))
      (node (ref "R13") (pin "2") (pinfunction "2_2") (pintype "passive"))
      (node (ref "R23") (pin "2") (pinfunction "2_2") (pintype "passive"))
      (node (ref "R24") (pin "2") (pinfunction "2_2") (pintype "passive"))
      (node (ref "R25") (pin "2") (pinfunction "2_2") (pintype "passive"))
      (node (ref "R26") (pin "2") (pinfunction "2_2") (pintype "passive"))
      (node (ref "R27") (pin "2") (pinfunction "2_2") (pintype "passive"))
      (node (ref "R28") (pin "2") (pinfunction "2_2") (pintype "passive"))
      (node (ref "R8") (pin "2") (pinfunction "2_2") (pintype "passive"))
      (node (ref "R9") (pin "2") (pinfunction "2_2") (pintype "passive"))
      (node (ref "U2") (pin "10") (pinfunction "VDD_10") (pintype "power_in"))
      (node (ref "U3") (pin "10") (pinfunction "VDD_10") (pintype "power_in"))
      (node (ref "U4") (pin "10") (pinfunction "VDD_10") (pintype "power_in"))
      (node (ref "U5") (pin "10") (pinfunction "VDD_10") (pintype "power_in"))
      (node (ref "U6") (pin "15") (pinfunction "VDD_15") (pintype "power_in"))
    )
    (net (code "60") (name "24V") (class "Default")
      (node (ref "C19") (pin "1") (pinfunction "1_1") (pintype "passive"))
      (node (ref "C21") (pin "1") (pinfunction "1_1") (pintype "passive"))
      (node (ref "C23") (pin "1") (pinfunction "1_1") (pintype "passive"))
      (node (ref "C24") (pin "2") (pinfunction "2_2") (pintype "passive"))
      (node (ref "C25") (pin "2") (pinfunction "2_2") (pintype "passive"))
      (node (ref "C26") (pin "2") (pinfunction "2_2") (pintype "passive"))
      (node (ref "C32") (pin "1") (pinfunction "1_1") (pintype "passive"))
      (node (ref "C33") (pin "2") (pinfunction "2_2") (pintype "passive"))
      (node (ref "C36") (pin "1") (pinfunction "+_1") (pintype "passive"))
      (node (ref "C37") (pin "1") (pinfunction "+_1") (pintype "passive"))
      (node (ref "C59") (pin "2") (pinfunction "2_2") (pintype "passive"))
      (node (ref "C60") (pin "2") (pinfunction "2_2") (pintype "passive"))
      (node (ref "C61") (pin "2") (pinfunction "2_2") (pintype "passive"))
      (node (ref "C62") (pin "2") (pinfunction "2_2") (pintype "passive"))
      (node (ref "U2") (pin "16") (pinfunction "VBB1_16") (pintype "passive"))
      (node (ref "U2") (pin "21") (pinfunction "VBB2_21") (pintype "passive"))
      (node (ref "U3") (pin "16") (pinfunction "VBB1_16") (pintype "passive"))
      (node (ref "U3") (pin "21") (pinfunction "VBB2_21") (pintype "passive"))
      (node (ref "U4") (pin "16") (pinfunction "VBB1_16") (pintype "passive"))
      (node (ref "U4") (pin "21") (pinfunction "VBB2_21") (pintype "passive"))
      (node (ref "U5") (pin "16") (pinfunction "VBB1_16") (pintype "passive"))
      (node (ref "U5") (pin "21") (pinfunction "VBB2_21") (pintype "passive"))
    )
    (net (code "61") (name "GND") (class "Default")
      (node (ref "C35") (pin "1") (pinfunction "1_1") (pintype "passive"))
      (node (ref "C36") (pin "2") (pinfunction "-_2") (pintype "passive"))
      (node (ref "C37") (pin "2") (pinfunction "-_2") (pintype "passive"))
      (node (ref "C63") (pin "1") (pinfunction "1_1") (pintype "passive"))
      (node (ref "C64") (pin "1") (pinfunction "1_1") (pintype "passive"))
      (node (ref "C65") (pin "1") (pinfunction "1_1") (pintype "passive"))
      (node (ref "C66") (pin "1") (pinfunction "1_1") (pintype "passive"))
      (node (ref "NT2") (pin "2") (pinfunction "2_2") (pintype "passive"))
      (node (ref "NT3") (pin "2") (pinfunction "2_2") (pintype "passive"))
      (node (ref "NT4") (pin "2") (pinfunction "2_2") (pintype "passive"))
      (node (ref "NT5") (pin "2") (pinfunction "2_2") (pintype "passive"))
      (node (ref "U2") (pin "25") (pinfunction "PAD_25") (pintype "power_in"))
      (node (ref "U3") (pin "25") (pinfunction "PAD_25") (pintype "power_in"))
      (node (ref "U4") (pin "25") (pinfunction "PAD_25") (pintype "power_in"))
      (node (ref "U5") (pin "25") (pinfunction "PAD_25") (pintype "power_in"))
      (node (ref "U6") (pin "1") (pinfunction "P3B_1") (pintype "passive"))
      (node (ref "U6") (pin "11") (pinfunction "P0B_11") (pintype "passive"))
      (node (ref "U6") (pin "12") (pinfunction "NC_12") (pintype "passive"))
      (node (ref "U6") (pin "14") (pinfunction "A1_14") (pintype "input"))
      (node (ref "U6") (pin "16") (pinfunction "P2B_16") (pintype "passive"))
      (node (ref "U6") (pin "2") (pinfunction "HVC/A0_2") (pintype "input"))
      (node (ref "U6") (pin "21") (pinfunction "EP_21") (pintype "passive"))
      (node (ref "U6") (pin "5") (pinfunction "VSS_5") (pintype "power_in"))
      (node (ref "U6") (pin "6") (pinfunction "P1B_6") (pintype "passive"))
    )
    (net (code "62") (name "Net-(U2-CP1)") (class "Default")
      (node (ref "C15") (pin "2") (pinfunction "2_2") (pintype "passive"))
      (node (ref "U2") (pin "1") (pinfunction "CP1_1") (pintype "power_in"))
    )
    (net (code "63") (name "Net-(U2-CP2)") (class "Default")
      (node (ref "C15") (pin "1") (pinfunction "1_1") (pintype "passive"))
      (node (ref "U2") (pin "2") (pinfunction "CP2_2") (pintype "power_in"))
    )
    (net (code "64") (name "Net-(U2-VCP)") (class "Default")
      (node (ref "C19") (pin "2") (pinfunction "2_2") (pintype "passive"))
      (node (ref "U2") (pin "3") (pinfunction "VCP_3") (pintype "passive"))
    )
    (net (code "65") (name "Net-(U2-VREG)") (class "Default")
      (node (ref "C27") (pin "1") (pinfunction "1_1") (pintype "passive"))
      (node (ref "U2") (pin "4") (pinfunction "VREG_4") (pintype "passive"))
    )
    (net (code "66") (name "Net-(U2-~{RESET})") (class "Default")
      (node (ref "R9") (pin "1") (pinfunction "1_1") (pintype "passive"))
      (node (ref "U2") (pin "7") (pinfunction "~{RESET}_7") (pintype "input"))
      (node (ref "U2") (pin "9") (pinfunction "~{SLEEP}_9") (pintype "input"))
    )
    (net (code "67") (name "Net-(U3-CP1)") (class "Default")
      (node (ref "C16") (pin "2") (pinfunction "2_2") (pintype "passive"))
      (node (ref "U3") (pin "1") (pinfunction "CP1_1") (pintype "power_in"))
    )
    (net (code "68") (name "Net-(U3-CP2)") (class "Default")
      (node (ref "C16") (pin "1") (pinfunction "1_1") (pintype "passive"))
      (node (ref "U3") (pin "2") (pinfunction "CP2_2") (pintype "power_in"))
    )
    (net (code "69") (name "Net-(U3-VCP)") (class "Default")
      (node (ref "C21") (pin "2") (pinfunction "2_2") (pintype "passive"))
      (node (ref "U3") (pin "3") (pinfunction "VCP_3") (pintype "passive"))
    )
    (net (code "70") (name "Net-(U3-VREG)") (class "Default")
      (node (ref "C28") (pin "1") (pinfunction "1_1") (pintype "passive"))
      (node (ref "U3") (pin "4") (pinfunction "VREG_4") (pintype "passive"))
    )
    (net (code "71") (name "Net-(U3-~{RESET})") (class "Default")
      (node (ref "R11") (pin "1") (pinfunction "1_1") (pintype "passive"))
      (node (ref "U3") (pin "7") (pinfunction "~{RESET}_7") (pintype "input"))
      (node (ref "U3") (pin "9") (pinfunction "~{SLEEP}_9") (pintype "input"))
    )
    (net (code "72") (name "Net-(U4-CP1)") (class "Default")
      (node (ref "C17") (pin "2") (pinfunction "2_2") (pintype "passive"))
      (node (ref "U4") (pin "1") (pinfunction "CP1_1") (pintype "power_in"))
    )
    (net (code "73") (name "Net-(U4-CP2)") (class "Default")
      (node (ref "C17") (pin "1") (pinfunction "1_1") (pintype "passive"))
      (node (ref "U4") (pin "2") (pinfunction "CP2_2") (pintype "power_in"))
    )
    (net (code "74") (name "Net-(U4-VCP)") (class "Default")
      (node (ref "C23") (pin "2") (pinfunction "2_2") (pintype "passive"))
      (node (ref "U4") (pin "3") (pinfunction "VCP_3") (pintype "passive"))
    )
    (net (code "75") (name "Net-(U4-VREG)") (class "Default")
      (node (ref "C29") (pin "1") (pinfunction "1_1") (pintype "passive"))
      (node (ref "U4") (pin "4") (pinfunction "VREG_4") (pintype "passive"))
    )
    (net (code "76") (name "Net-(U4-~{RESET})") (class "Default")
      (node (ref "R13") (pin "1") (pinfunction "1_1") (pintype "passive"))
      (node (ref "U4") (pin "7") (pinfunction "~{RESET}_7") (pintype "input"))
      (node (ref "U4") (pin "9") (pinfunction "~{SLEEP}_9") (pintype "input"))
    )
    (net (code "77") (name "Net-(U5-CP1)") (class "Default")
      (node (ref "C30") (pin "2") (pinfunction "2_2") (pintype "passive"))
      (node (ref "U5") (pin "1") (pinfunction "CP1_1") (pintype "power_in"))
    )
    (net (code "78") (name "Net-(U5-CP2)") (class "Default")
      (node (ref "C30") (pin "1") (pinfunction "1_1") (pintype "passive"))
      (node (ref "U5") (pin "2") (pinfunction "CP2_2") (pintype "power_in"))
    )
    (net (code "79") (name "Net-(U5-VCP)") (class "Default")
      (node (ref "C32") (pin "2") (pinfunction "2_2") (pintype "passive"))
      (node (ref "U5") (pin "3") (pinfunction "VCP_3") (pintype "passive"))
    )
    (net (code "80") (name "Net-(U5-VREG)") (class "Default")
      (node (ref "C34") (pin "1") (pinfunction "1_1") (pintype "passive"))
      (node (ref "U5") (pin "4") (pinfunction "VREG_4") (pintype "passive"))
    )
    (net (code "81") (name "Net-(U5-~{RESET})") (class "Default")
      (node (ref "R28") (pin "1") (pinfunction "1_1") (pintype "passive"))
      (node (ref "U5") (pin "7") (pinfunction "~{RESET}_7") (pintype "input"))
      (node (ref "U5") (pin "9") (pinfunction "~{SLEEP}_9") (pintype "input"))
    )
    (net (code "82") (name "Net-(U6-P0A)") (class "Default")
      (node (ref "R23") (pin "1") (pinfunction "1_1") (pintype "passive"))
      (node (ref "U6") (pin "18") (pinfunction "P2A_18") (pintype "passive"))
      (node (ref "U6") (pin "19") (pinfunction "P3A_19") (pintype "passive"))
      (node (ref "U6") (pin "8") (pinfunction "P1A_8") (pintype "passive"))
      (node (ref "U6") (pin "9") (pinfunction "P0A_9") (pintype "passive"))
    )
    (net (code "83") (name "Net-(U6-~{RESET})") (class "Default")
      (node (ref "R26") (pin "1") (pinfunction "1_1") (pintype "passive"))
      (node (ref "U6") (pin "13") (pinfunction "~{RESET}_13") (pintype "input"))
    )
  )
)
